# led_strip.net
KiCad netlist of a schematic drawn in EAGLE
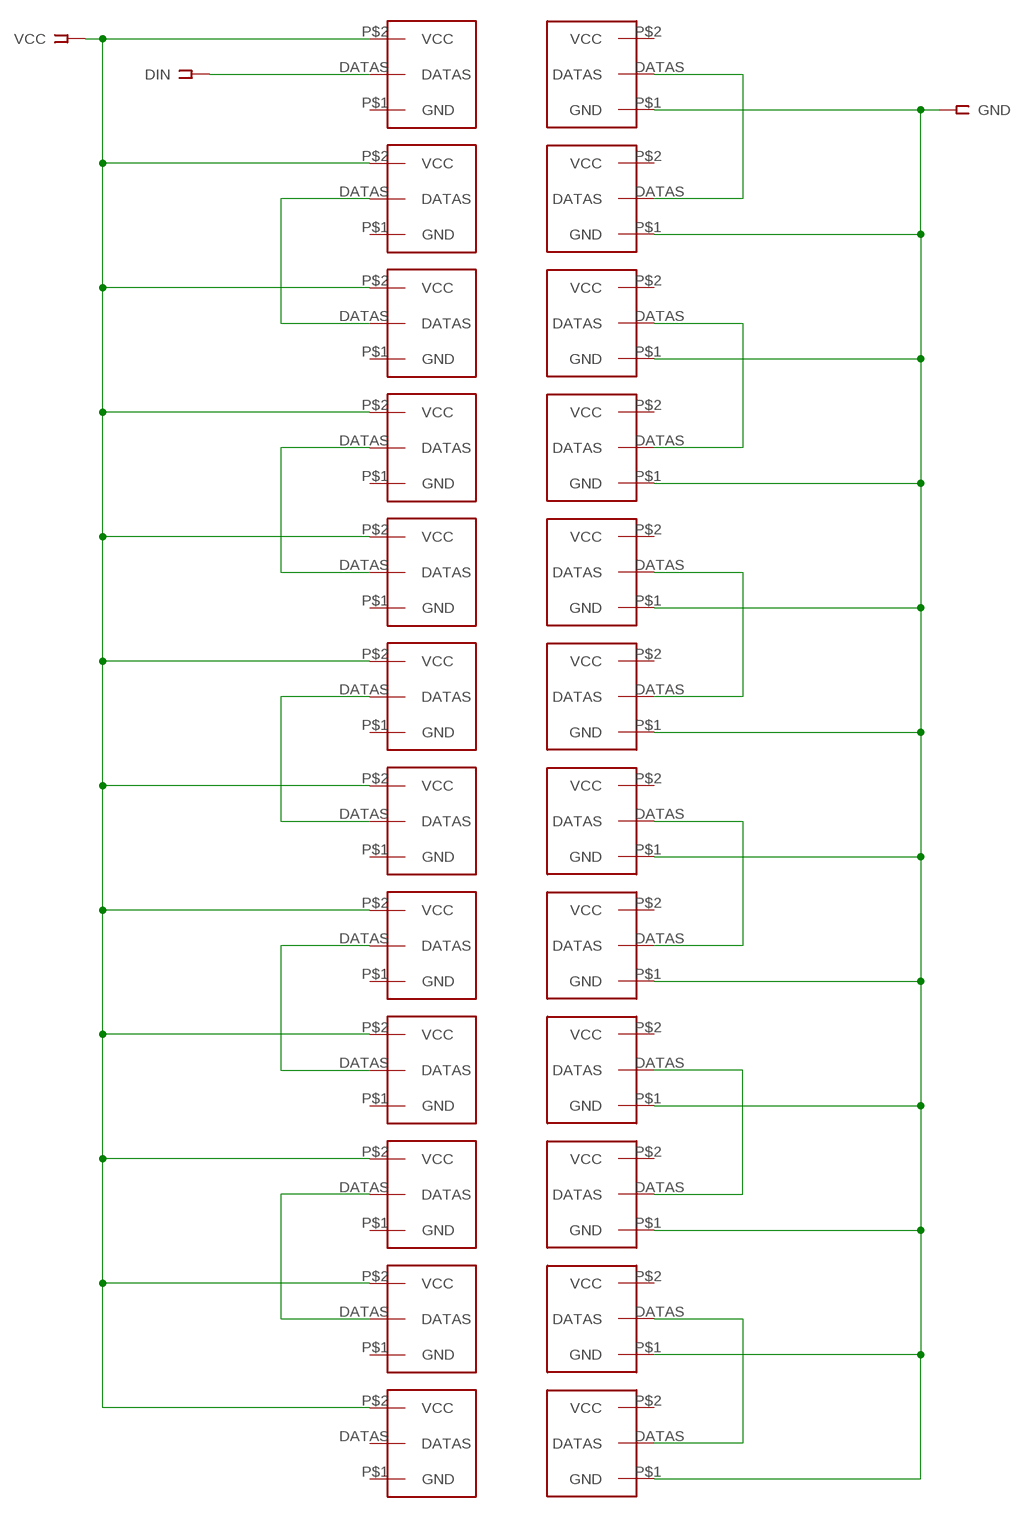
[diagram p0: schematic, sheet 1]

(export (version "E")
  (design (tool "Eeschema 10.0.6"))
  (components
    (comp (ref "1")
      (value "1")
      (footprint "eagle-import:LED_STRIP")
      (libsource (lib "eagle-import") (part "LED_STRIP"))
    )
    (comp (ref "2")
      (value "LED_STRIP")
      (footprint "eagle-import:LED_STRIP")
      (libsource (lib "eagle-import") (part "LED_STRIP"))
    )
    (comp (ref "3")
      (value "LED_STRIP")
      (footprint "eagle-import:LED_STRIP")
      (libsource (lib "eagle-import") (part "LED_STRIP"))
    )
    (comp (ref "4")
      (value "LED_STRIP")
      (footprint "eagle-import:LED_STRIP")
      (libsource (lib "eagle-import") (part "LED_STRIP"))
    )
    (comp (ref "5")
      (value "LED_STRIP")
      (footprint "eagle-import:LED_STRIP")
      (libsource (lib "eagle-import") (part "LED_STRIP"))
    )
    (comp (ref "6")
      (value "LED_STRIP")
      (footprint "eagle-import:LED_STRIP")
      (libsource (lib "eagle-import") (part "LED_STRIP"))
    )
    (comp (ref "7")
      (value "LED_STRIP")
      (footprint "eagle-import:LED_STRIP")
      (libsource (lib "eagle-import") (part "LED_STRIP"))
    )
    (comp (ref "8")
      (value "LED_STRIP")
      (footprint "eagle-import:LED_STRIP")
      (libsource (lib "eagle-import") (part "LED_STRIP"))
    )
    (comp (ref "9")
      (value "LED_STRIP")
      (footprint "eagle-import:LED_STRIP")
      (libsource (lib "eagle-import") (part "LED_STRIP"))
    )
    (comp (ref "10")
      (value "LED_STRIP")
      (footprint "eagle-import:LED_STRIP")
      (libsource (lib "eagle-import") (part "LED_STRIP"))
    )
    (comp (ref "11")
      (value "LED_STRIP")
      (footprint "eagle-import:LED_STRIP")
      (libsource (lib "eagle-import") (part "LED_STRIP"))
    )
    (comp (ref "12")
      (value "LED_STRIP")
      (footprint "eagle-import:LED_STRIP")
      (libsource (lib "eagle-import") (part "LED_STRIP"))
    )
    (comp (ref "13")
      (value "LED_STRIP")
      (footprint "eagle-import:LED_STRIP")
      (libsource (lib "eagle-import") (part "LED_STRIP"))
    )
    (comp (ref "14")
      (value "LED_STRIP")
      (footprint "eagle-import:LED_STRIP")
      (libsource (lib "eagle-import") (part "LED_STRIP"))
    )
    (comp (ref "15")
      (value "LED_STRIP")
      (footprint "eagle-import:LED_STRIP")
      (libsource (lib "eagle-import") (part "LED_STRIP"))
    )
    (comp (ref "16")
      (value "LED_STRIP")
      (footprint "eagle-import:LED_STRIP")
      (libsource (lib "eagle-import") (part "LED_STRIP"))
    )
    (comp (ref "17")
      (value "LED_STRIP")
      (footprint "eagle-import:LED_STRIP")
      (libsource (lib "eagle-import") (part "LED_STRIP"))
    )
    (comp (ref "18")
      (value "LED_STRIP")
      (footprint "eagle-import:LED_STRIP")
      (libsource (lib "eagle-import") (part "LED_STRIP"))
    )
    (comp (ref "19")
      (value "LED_STRIP")
      (footprint "eagle-import:LED_STRIP")
      (libsource (lib "eagle-import") (part "LED_STRIP"))
    )
    (comp (ref "20")
      (value "LED_STRIP")
      (footprint "eagle-import:LED_STRIP")
      (libsource (lib "eagle-import") (part "LED_STRIP"))
    )
    (comp (ref "21")
      (value "LED_STRIP")
      (footprint "eagle-import:LED_STRIP")
      (libsource (lib "eagle-import") (part "LED_STRIP"))
    )
    (comp (ref "22")
      (value "LED_STRIP")
      (footprint "eagle-import:LED_STRIP")
      (libsource (lib "eagle-import") (part "LED_STRIP"))
    )
    (comp (ref "23")
      (value "LED_STRIP")
      (footprint "eagle-import:LED_STRIP")
      (libsource (lib "eagle-import") (part "LED_STRIP"))
    )
    (comp (ref "24")
      (value "LED_STRIP")
      (footprint "eagle-import:LED_STRIP")
      (libsource (lib "eagle-import") (part "LED_STRIP"))
    )
    (comp (ref "DIN")
      (value "DATA")
      (footprint "eagle-import:SSW-101-02-S-S")
      (fields (field (name "MPN") "SSW-101-02-S-S"))
      (libsource (lib "eagle-import") (part "SSW-101-02-S-S"))
    )
    (comp (ref "GND")
      (value "GND")
      (footprint "eagle-import:SSW-101-02-S-S")
      (fields (field (name "MPN") "SSW-101-02-S-S"))
      (libsource (lib "eagle-import") (part "SSW-101-02-S-S"))
    )
    (comp (ref "VCC")
      (value "VCC")
      (footprint "eagle-import:SSW-101-02-S-S")
      (fields (field (name "MPN") "SSW-101-02-S-S"))
      (libsource (lib "eagle-import") (part "SSW-101-02-S-S"))
    )
  )
  (nets
    (net (code "1") (name "Net-(1-GND)") (class "Default")
      (node (ref "1") (pin "P$1") (pinfunction "GND_P$1") (pintype "bidirectional"))
      (node (ref "10") (pin "P$1") (pinfunction "GND_P$1") (pintype "bidirectional"))
      (node (ref "11") (pin "P$1") (pinfunction "GND_P$1") (pintype "bidirectional"))
      (node (ref "12") (pin "P$1") (pinfunction "GND_P$1") (pintype "bidirectional"))
      (node (ref "2") (pin "P$1") (pinfunction "GND_P$1") (pintype "bidirectional"))
      (node (ref "3") (pin "P$1") (pinfunction "GND_P$1") (pintype "bidirectional"))
      (node (ref "4") (pin "P$1") (pinfunction "GND_P$1") (pintype "bidirectional"))
      (node (ref "5") (pin "P$1") (pinfunction "GND_P$1") (pintype "bidirectional"))
      (node (ref "6") (pin "P$1") (pinfunction "GND_P$1") (pintype "bidirectional"))
      (node (ref "7") (pin "P$1") (pinfunction "GND_P$1") (pintype "bidirectional"))
      (node (ref "8") (pin "P$1") (pinfunction "GND_P$1") (pintype "bidirectional"))
      (node (ref "9") (pin "P$1") (pinfunction "GND_P$1") (pintype "bidirectional"))
      (node (ref "GND") (pin "1") (pinfunction "1_1") (pintype "passive"))
    )
    (net (code "2") (name "Net-(1-PadDATAS)") (class "Default")
      (node (ref "1") (pin "DATAS") (pinfunction "DATAS_DATAS") (pintype "bidirectional"))
      (node (ref "2") (pin "DATAS") (pinfunction "DATAS_DATAS") (pintype "bidirectional"))
    )
    (net (code "3") (name "Net-(3-PadDATAS)") (class "Default")
      (node (ref "3") (pin "DATAS") (pinfunction "DATAS_DATAS") (pintype "bidirectional"))
      (node (ref "4") (pin "DATAS") (pinfunction "DATAS_DATAS") (pintype "bidirectional"))
    )
    (net (code "4") (name "Net-(5-PadDATAS)") (class "Default")
      (node (ref "5") (pin "DATAS") (pinfunction "DATAS_DATAS") (pintype "bidirectional"))
      (node (ref "6") (pin "DATAS") (pinfunction "DATAS_DATAS") (pintype "bidirectional"))
    )
    (net (code "5") (name "Net-(7-PadDATAS)") (class "Default")
      (node (ref "7") (pin "DATAS") (pinfunction "DATAS_DATAS") (pintype "bidirectional"))
      (node (ref "8") (pin "DATAS") (pinfunction "DATAS_DATAS") (pintype "bidirectional"))
    )
    (net (code "6") (name "Net-(10-PadDATAS)") (class "Default")
      (node (ref "10") (pin "DATAS") (pinfunction "DATAS_DATAS") (pintype "bidirectional"))
      (node (ref "9") (pin "DATAS") (pinfunction "DATAS_DATAS") (pintype "bidirectional"))
    )
    (net (code "7") (name "Net-(11-PadDATAS)") (class "Default")
      (node (ref "11") (pin "DATAS") (pinfunction "DATAS_DATAS") (pintype "bidirectional"))
      (node (ref "12") (pin "DATAS") (pinfunction "DATAS_DATAS") (pintype "bidirectional"))
    )
    (net (code "8") (name "Net-(13-PadDATAS)") (class "Default")
      (node (ref "13") (pin "DATAS") (pinfunction "DATAS_DATAS") (pintype "bidirectional"))
      (node (ref "DIN") (pin "1") (pinfunction "1_1") (pintype "passive"))
    )
    (net (code "9") (name "Net-(13-VCC)") (class "Default")
      (node (ref "13") (pin "P$2") (pinfunction "VCC_P$2") (pintype "bidirectional"))
      (node (ref "14") (pin "P$2") (pinfunction "VCC_P$2") (pintype "bidirectional"))
      (node (ref "15") (pin "P$2") (pinfunction "VCC_P$2") (pintype "bidirectional"))
      (node (ref "16") (pin "P$2") (pinfunction "VCC_P$2") (pintype "bidirectional"))
      (node (ref "17") (pin "P$2") (pinfunction "VCC_P$2") (pintype "bidirectional"))
      (node (ref "18") (pin "P$2") (pinfunction "VCC_P$2") (pintype "bidirectional"))
      (node (ref "19") (pin "P$2") (pinfunction "VCC_P$2") (pintype "bidirectional"))
      (node (ref "20") (pin "P$2") (pinfunction "VCC_P$2") (pintype "bidirectional"))
      (node (ref "21") (pin "P$2") (pinfunction "VCC_P$2") (pintype "bidirectional"))
      (node (ref "22") (pin "P$2") (pinfunction "VCC_P$2") (pintype "bidirectional"))
      (node (ref "23") (pin "P$2") (pinfunction "VCC_P$2") (pintype "bidirectional"))
      (node (ref "24") (pin "P$2") (pinfunction "VCC_P$2") (pintype "bidirectional"))
      (node (ref "VCC") (pin "1") (pinfunction "1_1") (pintype "passive"))
    )
    (net (code "10") (name "Net-(14-PadDATAS)") (class "Default")
      (node (ref "14") (pin "DATAS") (pinfunction "DATAS_DATAS") (pintype "bidirectional"))
      (node (ref "15") (pin "DATAS") (pinfunction "DATAS_DATAS") (pintype "bidirectional"))
    )
    (net (code "11") (name "Net-(16-PadDATAS)") (class "Default")
      (node (ref "16") (pin "DATAS") (pinfunction "DATAS_DATAS") (pintype "bidirectional"))
      (node (ref "17") (pin "DATAS") (pinfunction "DATAS_DATAS") (pintype "bidirectional"))
    )
    (net (code "12") (name "Net-(18-PadDATAS)") (class "Default")
      (node (ref "18") (pin "DATAS") (pinfunction "DATAS_DATAS") (pintype "bidirectional"))
      (node (ref "19") (pin "DATAS") (pinfunction "DATAS_DATAS") (pintype "bidirectional"))
    )
    (net (code "13") (name "Net-(20-PadDATAS)") (class "Default")
      (node (ref "20") (pin "DATAS") (pinfunction "DATAS_DATAS") (pintype "bidirectional"))
      (node (ref "21") (pin "DATAS") (pinfunction "DATAS_DATAS") (pintype "bidirectional"))
    )
    (net (code "14") (name "Net-(22-PadDATAS)") (class "Default")
      (node (ref "22") (pin "DATAS") (pinfunction "DATAS_DATAS") (pintype "bidirectional"))
      (node (ref "23") (pin "DATAS") (pinfunction "DATAS_DATAS") (pintype "bidirectional"))
    )
    (net (code "15") (name "unconnected-(1-VCC-PadP$2)") (class "Default")
      (node (ref "1") (pin "P$2") (pinfunction "VCC_P$2") (pintype "bidirectional"))
    )
    (net (code "16") (name "unconnected-(2-VCC-PadP$2)") (class "Default")
      (node (ref "2") (pin "P$2") (pinfunction "VCC_P$2") (pintype "bidirectional"))
    )
    (net (code "17") (name "unconnected-(3-VCC-PadP$2)") (class "Default")
      (node (ref "3") (pin "P$2") (pinfunction "VCC_P$2") (pintype "bidirectional"))
    )
    (net (code "18") (name "unconnected-(4-VCC-PadP$2)") (class "Default")
      (node (ref "4") (pin "P$2") (pinfunction "VCC_P$2") (pintype "bidirectional"))
    )
    (net (code "19") (name "unconnected-(5-VCC-PadP$2)") (class "Default")
      (node (ref "5") (pin "P$2") (pinfunction "VCC_P$2") (pintype "bidirectional"))
    )
    (net (code "20") (name "unconnected-(6-VCC-PadP$2)") (class "Default")
      (node (ref "6") (pin "P$2") (pinfunction "VCC_P$2") (pintype "bidirectional"))
    )
    (net (code "21") (name "unconnected-(7-VCC-PadP$2)") (class "Default")
      (node (ref "7") (pin "P$2") (pinfunction "VCC_P$2") (pintype "bidirectional"))
    )
    (net (code "22") (name "unconnected-(8-VCC-PadP$2)") (class "Default")
      (node (ref "8") (pin "P$2") (pinfunction "VCC_P$2") (pintype "bidirectional"))
    )
    (net (code "23") (name "unconnected-(9-VCC-PadP$2)") (class "Default")
      (node (ref "9") (pin "P$2") (pinfunction "VCC_P$2") (pintype "bidirectional"))
    )
    (net (code "24") (name "unconnected-(10-VCC-PadP$2)") (class "Default")
      (node (ref "10") (pin "P$2") (pinfunction "VCC_P$2") (pintype "bidirectional"))
    )
    (net (code "25") (name "unconnected-(11-VCC-PadP$2)") (class "Default")
      (node (ref "11") (pin "P$2") (pinfunction "VCC_P$2") (pintype "bidirectional"))
    )
    (net (code "26") (name "unconnected-(12-VCC-PadP$2)") (class "Default")
      (node (ref "12") (pin "P$2") (pinfunction "VCC_P$2") (pintype "bidirectional"))
    )
    (net (code "27") (name "unconnected-(13-GND-PadP$1)") (class "Default")
      (node (ref "13") (pin "P$1") (pinfunction "GND_P$1") (pintype "bidirectional"))
    )
    (net (code "28") (name "unconnected-(14-GND-PadP$1)") (class "Default")
      (node (ref "14") (pin "P$1") (pinfunction "GND_P$1") (pintype "bidirectional"))
    )
    (net (code "29") (name "unconnected-(15-GND-PadP$1)") (class "Default")
      (node (ref "15") (pin "P$1") (pinfunction "GND_P$1") (pintype "bidirectional"))
    )
    (net (code "30") (name "unconnected-(16-GND-PadP$1)") (class "Default")
      (node (ref "16") (pin "P$1") (pinfunction "GND_P$1") (pintype "bidirectional"))
    )
    (net (code "31") (name "unconnected-(17-GND-PadP$1)") (class "Default")
      (node (ref "17") (pin "P$1") (pinfunction "GND_P$1") (pintype "bidirectional"))
    )
    (net (code "32") (name "unconnected-(18-GND-PadP$1)") (class "Default")
      (node (ref "18") (pin "P$1") (pinfunction "GND_P$1") (pintype "bidirectional"))
    )
    (net (code "33") (name "unconnected-(19-GND-PadP$1)") (class "Default")
      (node (ref "19") (pin "P$1") (pinfunction "GND_P$1") (pintype "bidirectional"))
    )
    (net (code "34") (name "unconnected-(20-GND-PadP$1)") (class "Default")
      (node (ref "20") (pin "P$1") (pinfunction "GND_P$1") (pintype "bidirectional"))
    )
    (net (code "35") (name "unconnected-(21-GND-PadP$1)") (class "Default")
      (node (ref "21") (pin "P$1") (pinfunction "GND_P$1") (pintype "bidirectional"))
    )
    (net (code "36") (name "unconnected-(22-GND-PadP$1)") (class "Default")
      (node (ref "22") (pin "P$1") (pinfunction "GND_P$1") (pintype "bidirectional"))
    )
    (net (code "37") (name "unconnected-(23-GND-PadP$1)") (class "Default")
      (node (ref "23") (pin "P$1") (pinfunction "GND_P$1") (pintype "bidirectional"))
    )
    (net (code "38") (name "unconnected-(24-GND-PadP$1)") (class "Default")
      (node (ref "24") (pin "P$1") (pinfunction "GND_P$1") (pintype "bidirectional"))
    )
    (net (code "39") (name "unconnected-(24-PadDATAS)") (class "Default")
      (node (ref "24") (pin "DATAS") (pinfunction "DATAS_DATAS") (pintype "bidirectional"))
    )
  )
)
